# BK1096_Connector.net
KiCad netlist of a schematic drawn in Altium Designer
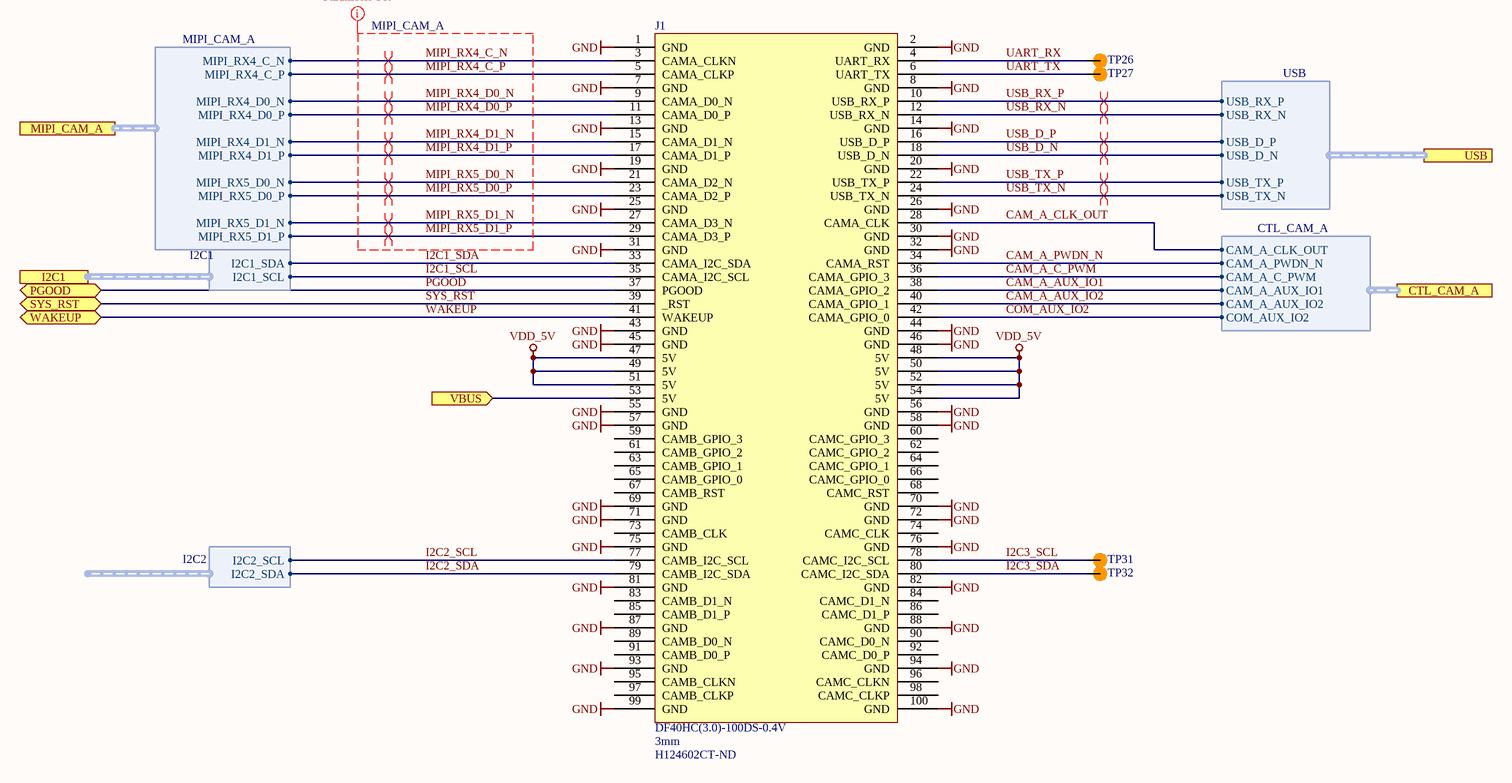
[diagram p0: BK1096_Connector.SchDoc]

(export (version "E")
  (design (tool "Eeschema 10.0.6"))
  (components
    (comp (ref "J1")
      (value "DF40HC(3.0)-100DS-0.4V")
      (footprint "Luxonis:DF40HC-3.0-100DS-0.4V")
      (description "CONN RCPT 100POS 0.4MM SMD GOLD")
      (fields
        (field (name "MATED STACKING HEIGHTS") "3mm")
        (field (name "SUPPLIER PART NUMBER 1") "H124602CT-ND")
      )
      (libsource (lib "Luxonis") (part "DF40HC(3.0)-100DS-0.4V"))
    )
    (comp (ref "TP26")
      (value "TP_SMD")
      (footprint "TP_0.75MM_SMD_NO-SILK")
      (description "circular pad test point, SMD")
      (libsource (lib "Luxonis") (part "TP_SMD"))
    )
    (comp (ref "TP27")
      (value "TP_SMD")
      (footprint "TP_0.75MM_SMD_NO-SILK")
      (description "circular pad test point, SMD")
      (libsource (lib "Luxonis") (part "TP_SMD"))
    )
    (comp (ref "TP31")
      (value "TP_SMD")
      (footprint "TP_0.75MM_SMD_NO-SILK")
      (description "circular pad test point, SMD")
      (libsource (lib "Luxonis") (part "TP_SMD"))
    )
    (comp (ref "TP32")
      (value "TP_SMD")
      (footprint "TP_0.75MM_SMD_NO-SILK")
      (description "circular pad test point, SMD")
      (libsource (lib "Luxonis") (part "TP_SMD"))
    )
  )
  (nets
    (net (code "6") (name "/CAM_A_AUX_IO1") (class "Default")
      (node (ref "J1") (pin "38") (pinfunction "CAMA_GPIO_2_38") (pintype "passive"))
    )
    (net (code "7") (name "/CAM_A_AUX_IO2") (class "Default")
      (node (ref "J1") (pin "40") (pinfunction "CAMA_GPIO_1_40") (pintype "passive"))
    )
    (net (code "8") (name "/CAM_A_CLK_OUT") (class "Default")
      (node (ref "J1") (pin "28") (pinfunction "CAMA_CLK_28") (pintype "passive"))
    )
    (net (code "9") (name "/CAM_A_C_PWM") (class "Default")
      (node (ref "J1") (pin "36") (pinfunction "CAMA_GPIO_3_36") (pintype "passive"))
    )
    (net (code "10") (name "/CAM_A_PWDN_N") (class "Default")
      (node (ref "J1") (pin "34") (pinfunction "CAMA_RST_34") (pintype "passive"))
    )
    (net (code "11") (name "/COM_AUX_IO2") (class "Default")
      (node (ref "J1") (pin "42") (pinfunction "CAMA_GPIO_0_42") (pintype "passive"))
    )
    (net (code "12") (name "/I2C1_SCL") (class "Default")
      (node (ref "J1") (pin "35") (pinfunction "CAMA_I2C_SCL_35") (pintype "passive"))
    )
    (net (code "13") (name "/I2C1_SDA") (class "Default")
      (node (ref "J1") (pin "33") (pinfunction "CAMA_I2C_SDA_33") (pintype "passive"))
    )
    (net (code "14") (name "/I2C2_SCL") (class "Default")
      (node (ref "J1") (pin "77") (pinfunction "CAMB_I2C_SCL_77") (pintype "passive"))
    )
    (net (code "15") (name "/I2C2_SDA") (class "Default")
      (node (ref "J1") (pin "79") (pinfunction "CAMB_I2C_SDA_79") (pintype "passive"))
    )
    (net (code "16") (name "/I2C3_SCL") (class "Default")
      (node (ref "J1") (pin "78") (pinfunction "CAMC_I2C_SCL_78") (pintype "passive"))
      (node (ref "TP31") (pin "1") (pintype "passive"))
    )
    (net (code "17") (name "/I2C3_SDA") (class "Default")
      (node (ref "J1") (pin "80") (pinfunction "CAMC_I2C_SDA_80") (pintype "passive"))
      (node (ref "TP32") (pin "1") (pintype "passive"))
    )
    (net (code "19") (name "/MIPI_RX4_C_N") (class "Default")
      (node (ref "J1") (pin "3") (pinfunction "CAMA_CLKN_3") (pintype "passive"))
    )
    (net (code "20") (name "/MIPI_RX4_C_P") (class "Default")
      (node (ref "J1") (pin "5") (pinfunction "CAMA_CLKP_5") (pintype "passive"))
    )
    (net (code "21") (name "/MIPI_RX4_D0_N") (class "Default")
      (node (ref "J1") (pin "9") (pinfunction "CAMA_D0_N_9") (pintype "passive"))
    )
    (net (code "22") (name "/MIPI_RX4_D0_P") (class "Default")
      (node (ref "J1") (pin "11") (pinfunction "CAMA_D0_P_11") (pintype "passive"))
    )
    (net (code "23") (name "/MIPI_RX4_D1_N") (class "Default")
      (node (ref "J1") (pin "15") (pinfunction "CAMA_D1_N_15") (pintype "passive"))
    )
    (net (code "24") (name "/MIPI_RX4_D1_P") (class "Default")
      (node (ref "J1") (pin "17") (pinfunction "CAMA_D1_P_17") (pintype "passive"))
    )
    (net (code "25") (name "/MIPI_RX5_D0_N") (class "Default")
      (node (ref "J1") (pin "21") (pinfunction "CAMA_D2_N_21") (pintype "passive"))
    )
    (net (code "26") (name "/MIPI_RX5_D0_P") (class "Default")
      (node (ref "J1") (pin "23") (pinfunction "CAMA_D2_P_23") (pintype "passive"))
    )
    (net (code "27") (name "/MIPI_RX5_D1_N") (class "Default")
      (node (ref "J1") (pin "27") (pinfunction "CAMA_D3_N_27") (pintype "passive"))
    )
    (net (code "28") (name "/MIPI_RX5_D1_P") (class "Default")
      (node (ref "J1") (pin "29") (pinfunction "CAMA_D3_P_29") (pintype "passive"))
    )
    (net (code "29") (name "/PGOOD") (class "Default")
      (node (ref "J1") (pin "37") (pinfunction "PGOOD_37") (pintype "passive"))
    )
    (net (code "30") (name "/SYS_RST") (class "Default")
      (node (ref "J1") (pin "39") (pinfunction "_RST_39") (pintype "passive"))
    )
    (net (code "31") (name "/UART_RX") (class "Default")
      (node (ref "J1") (pin "4") (pinfunction "UART_RX_4") (pintype "passive"))
      (node (ref "TP26") (pin "1") (pintype "passive"))
    )
    (net (code "32") (name "/UART_TX") (class "Default")
      (node (ref "J1") (pin "6") (pinfunction "UART_TX_6") (pintype "passive"))
      (node (ref "TP27") (pin "1") (pintype "passive"))
    )
    (net (code "33") (name "/USB_D_N") (class "Default")
      (node (ref "J1") (pin "18") (pinfunction "USB_D_N_18") (pintype "passive"))
    )
    (net (code "34") (name "/USB_D_P") (class "Default")
      (node (ref "J1") (pin "16") (pinfunction "USB_D_P_16") (pintype "passive"))
    )
    (net (code "35") (name "/USB_RX_N") (class "Default")
      (node (ref "J1") (pin "12") (pinfunction "USB_RX_N_12") (pintype "passive"))
    )
    (net (code "36") (name "/USB_RX_P") (class "Default")
      (node (ref "J1") (pin "10") (pinfunction "USB_RX_P_10") (pintype "passive"))
    )
    (net (code "37") (name "/USB_TX_N") (class "Default")
      (node (ref "J1") (pin "24") (pinfunction "USB_TX_N_24") (pintype "passive"))
    )
    (net (code "38") (name "/USB_TX_P") (class "Default")
      (node (ref "J1") (pin "22") (pinfunction "USB_TX_P_22") (pintype "passive"))
    )
    (net (code "39") (name "/VBUS") (class "Default")
      (node (ref "J1") (pin "53") (pinfunction "5V_53") (pintype "passive"))
    )
    (net (code "40") (name "/WAKEUP") (class "Default")
      (node (ref "J1") (pin "41") (pinfunction "WAKEUP_41") (pintype "passive"))
    )
    (net (code "45") (name "GND") (class "Default")
      (node (ref "J1") (pin "1") (pinfunction "GND_1") (pintype "passive"))
      (node (ref "J1") (pin "100") (pinfunction "GND_100") (pintype "passive"))
      (node (ref "J1") (pin "13") (pinfunction "GND_13") (pintype "passive"))
      (node (ref "J1") (pin "14") (pinfunction "GND_14") (pintype "passive"))
      (node (ref "J1") (pin "19") (pinfunction "GND_19") (pintype "passive"))
      (node (ref "J1") (pin "2") (pinfunction "GND_2") (pintype "passive"))
      (node (ref "J1") (pin "20") (pinfunction "GND_20") (pintype "passive"))
      (node (ref "J1") (pin "25") (pinfunction "GND_25") (pintype "passive"))
      (node (ref "J1") (pin "26") (pinfunction "GND_26") (pintype "passive"))
      (node (ref "J1") (pin "30") (pinfunction "GND_30") (pintype "passive"))
      (node (ref "J1") (pin "31") (pinfunction "GND_31") (pintype "passive"))
      (node (ref "J1") (pin "32") (pinfunction "GND_32") (pintype "passive"))
      (node (ref "J1") (pin "43") (pinfunction "GND_43") (pintype "passive"))
      (node (ref "J1") (pin "44") (pinfunction "GND_44") (pintype "passive"))
      (node (ref "J1") (pin "45") (pinfunction "GND_45") (pintype "passive"))
      (node (ref "J1") (pin "46") (pinfunction "GND_46") (pintype "passive"))
      (node (ref "J1") (pin "55") (pinfunction "GND_55") (pintype "passive"))
      (node (ref "J1") (pin "56") (pinfunction "GND_56") (pintype "passive"))
      (node (ref "J1") (pin "57") (pinfunction "GND_57") (pintype "passive"))
      (node (ref "J1") (pin "58") (pinfunction "GND_58") (pintype "passive"))
      (node (ref "J1") (pin "69") (pinfunction "GND_69") (pintype "passive"))
      (node (ref "J1") (pin "7") (pinfunction "GND_7") (pintype "passive"))
      (node (ref "J1") (pin "70") (pinfunction "GND_70") (pintype "passive"))
      (node (ref "J1") (pin "71") (pinfunction "GND_71") (pintype "passive"))
      (node (ref "J1") (pin "72") (pinfunction "GND_72") (pintype "passive"))
      (node (ref "J1") (pin "75") (pinfunction "GND_75") (pintype "passive"))
      (node (ref "J1") (pin "76") (pinfunction "GND_76") (pintype "passive"))
      (node (ref "J1") (pin "8") (pinfunction "GND_8") (pintype "passive"))
      (node (ref "J1") (pin "81") (pinfunction "GND_81") (pintype "passive"))
      (node (ref "J1") (pin "82") (pinfunction "GND_82") (pintype "passive"))
      (node (ref "J1") (pin "87") (pinfunction "GND_87") (pintype "passive"))
      (node (ref "J1") (pin "88") (pinfunction "GND_88") (pintype "passive"))
      (node (ref "J1") (pin "93") (pinfunction "GND_93") (pintype "passive"))
      (node (ref "J1") (pin "94") (pinfunction "GND_94") (pintype "passive"))
      (node (ref "J1") (pin "99") (pinfunction "GND_99") (pintype "passive"))
    )
    (net (code "46") (name "VDD_5V") (class "Default")
      (node (ref "J1") (pin "47") (pinfunction "5V_47") (pintype "passive"))
      (node (ref "J1") (pin "48") (pinfunction "5V_48") (pintype "passive"))
      (node (ref "J1") (pin "49") (pinfunction "5V_49") (pintype "passive"))
      (node (ref "J1") (pin "50") (pinfunction "5V_50") (pintype "passive"))
      (node (ref "J1") (pin "51") (pinfunction "5V_51") (pintype "passive"))
      (node (ref "J1") (pin "52") (pinfunction "5V_52") (pintype "passive"))
      (node (ref "J1") (pin "54") (pinfunction "5V_54") (pintype "passive"))
    )
    (net (code "47") (name "unconnected-(J1-CAMB_CLK-Pad73)") (class "Default")
      (node (ref "J1") (pin "73") (pinfunction "CAMB_CLK_73") (pintype "passive"))
    )
    (net (code "48") (name "unconnected-(J1-CAMB_CLKN-Pad95)") (class "Default")
      (node (ref "J1") (pin "95") (pinfunction "CAMB_CLKN_95") (pintype "passive"))
    )
    (net (code "49") (name "unconnected-(J1-CAMB_CLKP-Pad97)") (class "Default")
      (node (ref "J1") (pin "97") (pinfunction "CAMB_CLKP_97") (pintype "passive"))
    )
    (net (code "50") (name "unconnected-(J1-CAMB_D0_N-Pad89)") (class "Default")
      (node (ref "J1") (pin "89") (pinfunction "CAMB_D0_N_89") (pintype "passive"))
    )
    (net (code "51") (name "unconnected-(J1-CAMB_D0_P-Pad91)") (class "Default")
      (node (ref "J1") (pin "91") (pinfunction "CAMB_D0_P_91") (pintype "passive"))
    )
    (net (code "52") (name "unconnected-(J1-CAMB_D1_N-Pad83)") (class "Default")
      (node (ref "J1") (pin "83") (pinfunction "CAMB_D1_N_83") (pintype "passive"))
    )
    (net (code "53") (name "unconnected-(J1-CAMB_D1_P-Pad85)") (class "Default")
      (node (ref "J1") (pin "85") (pinfunction "CAMB_D1_P_85") (pintype "passive"))
    )
    (net (code "54") (name "unconnected-(J1-CAMB_GPIO_0-Pad65)") (class "Default")
      (node (ref "J1") (pin "65") (pinfunction "CAMB_GPIO_0_65") (pintype "passive"))
    )
    (net (code "55") (name "unconnected-(J1-CAMB_GPIO_1-Pad63)") (class "Default")
      (node (ref "J1") (pin "63") (pinfunction "CAMB_GPIO_1_63") (pintype "passive"))
    )
    (net (code "56") (name "unconnected-(J1-CAMB_GPIO_2-Pad61)") (class "Default")
      (node (ref "J1") (pin "61") (pinfunction "CAMB_GPIO_2_61") (pintype "passive"))
    )
    (net (code "57") (name "unconnected-(J1-CAMB_GPIO_3-Pad59)") (class "Default")
      (node (ref "J1") (pin "59") (pinfunction "CAMB_GPIO_3_59") (pintype "passive"))
    )
    (net (code "58") (name "unconnected-(J1-CAMB_RST-Pad67)") (class "Default")
      (node (ref "J1") (pin "67") (pinfunction "CAMB_RST_67") (pintype "passive"))
    )
    (net (code "59") (name "unconnected-(J1-CAMC_CLK-Pad74)") (class "Default")
      (node (ref "J1") (pin "74") (pinfunction "CAMC_CLK_74") (pintype "passive"))
    )
    (net (code "60") (name "unconnected-(J1-CAMC_CLKN-Pad96)") (class "Default")
      (node (ref "J1") (pin "96") (pinfunction "CAMC_CLKN_96") (pintype "passive"))
    )
    (net (code "61") (name "unconnected-(J1-CAMC_CLKP-Pad98)") (class "Default")
      (node (ref "J1") (pin "98") (pinfunction "CAMC_CLKP_98") (pintype "passive"))
    )
    (net (code "62") (name "unconnected-(J1-CAMC_D0_N-Pad90)") (class "Default")
      (node (ref "J1") (pin "90") (pinfunction "CAMC_D0_N_90") (pintype "passive"))
    )
    (net (code "63") (name "unconnected-(J1-CAMC_D0_P-Pad92)") (class "Default")
      (node (ref "J1") (pin "92") (pinfunction "CAMC_D0_P_92") (pintype "passive"))
    )
    (net (code "64") (name "unconnected-(J1-CAMC_D1_N-Pad84)") (class "Default")
      (node (ref "J1") (pin "84") (pinfunction "CAMC_D1_N_84") (pintype "passive"))
    )
    (net (code "65") (name "unconnected-(J1-CAMC_D1_P-Pad86)") (class "Default")
      (node (ref "J1") (pin "86") (pinfunction "CAMC_D1_P_86") (pintype "passive"))
    )
    (net (code "66") (name "unconnected-(J1-CAMC_GPIO_0-Pad66)") (class "Default")
      (node (ref "J1") (pin "66") (pinfunction "CAMC_GPIO_0_66") (pintype "passive"))
    )
    (net (code "67") (name "unconnected-(J1-CAMC_GPIO_1-Pad64)") (class "Default")
      (node (ref "J1") (pin "64") (pinfunction "CAMC_GPIO_1_64") (pintype "passive"))
    )
    (net (code "68") (name "unconnected-(J1-CAMC_GPIO_2-Pad62)") (class "Default")
      (node (ref "J1") (pin "62") (pinfunction "CAMC_GPIO_2_62") (pintype "passive"))
    )
    (net (code "69") (name "unconnected-(J1-CAMC_GPIO_3-Pad60)") (class "Default")
      (node (ref "J1") (pin "60") (pinfunction "CAMC_GPIO_3_60") (pintype "passive"))
    )
    (net (code "70") (name "unconnected-(J1-CAMC_RST-Pad68)") (class "Default")
      (node (ref "J1") (pin "68") (pinfunction "CAMC_RST_68") (pintype "passive"))
    )
  )
)
